# Carrier_Board.net
KiCad netlist of a schematic drawn in EAGLE
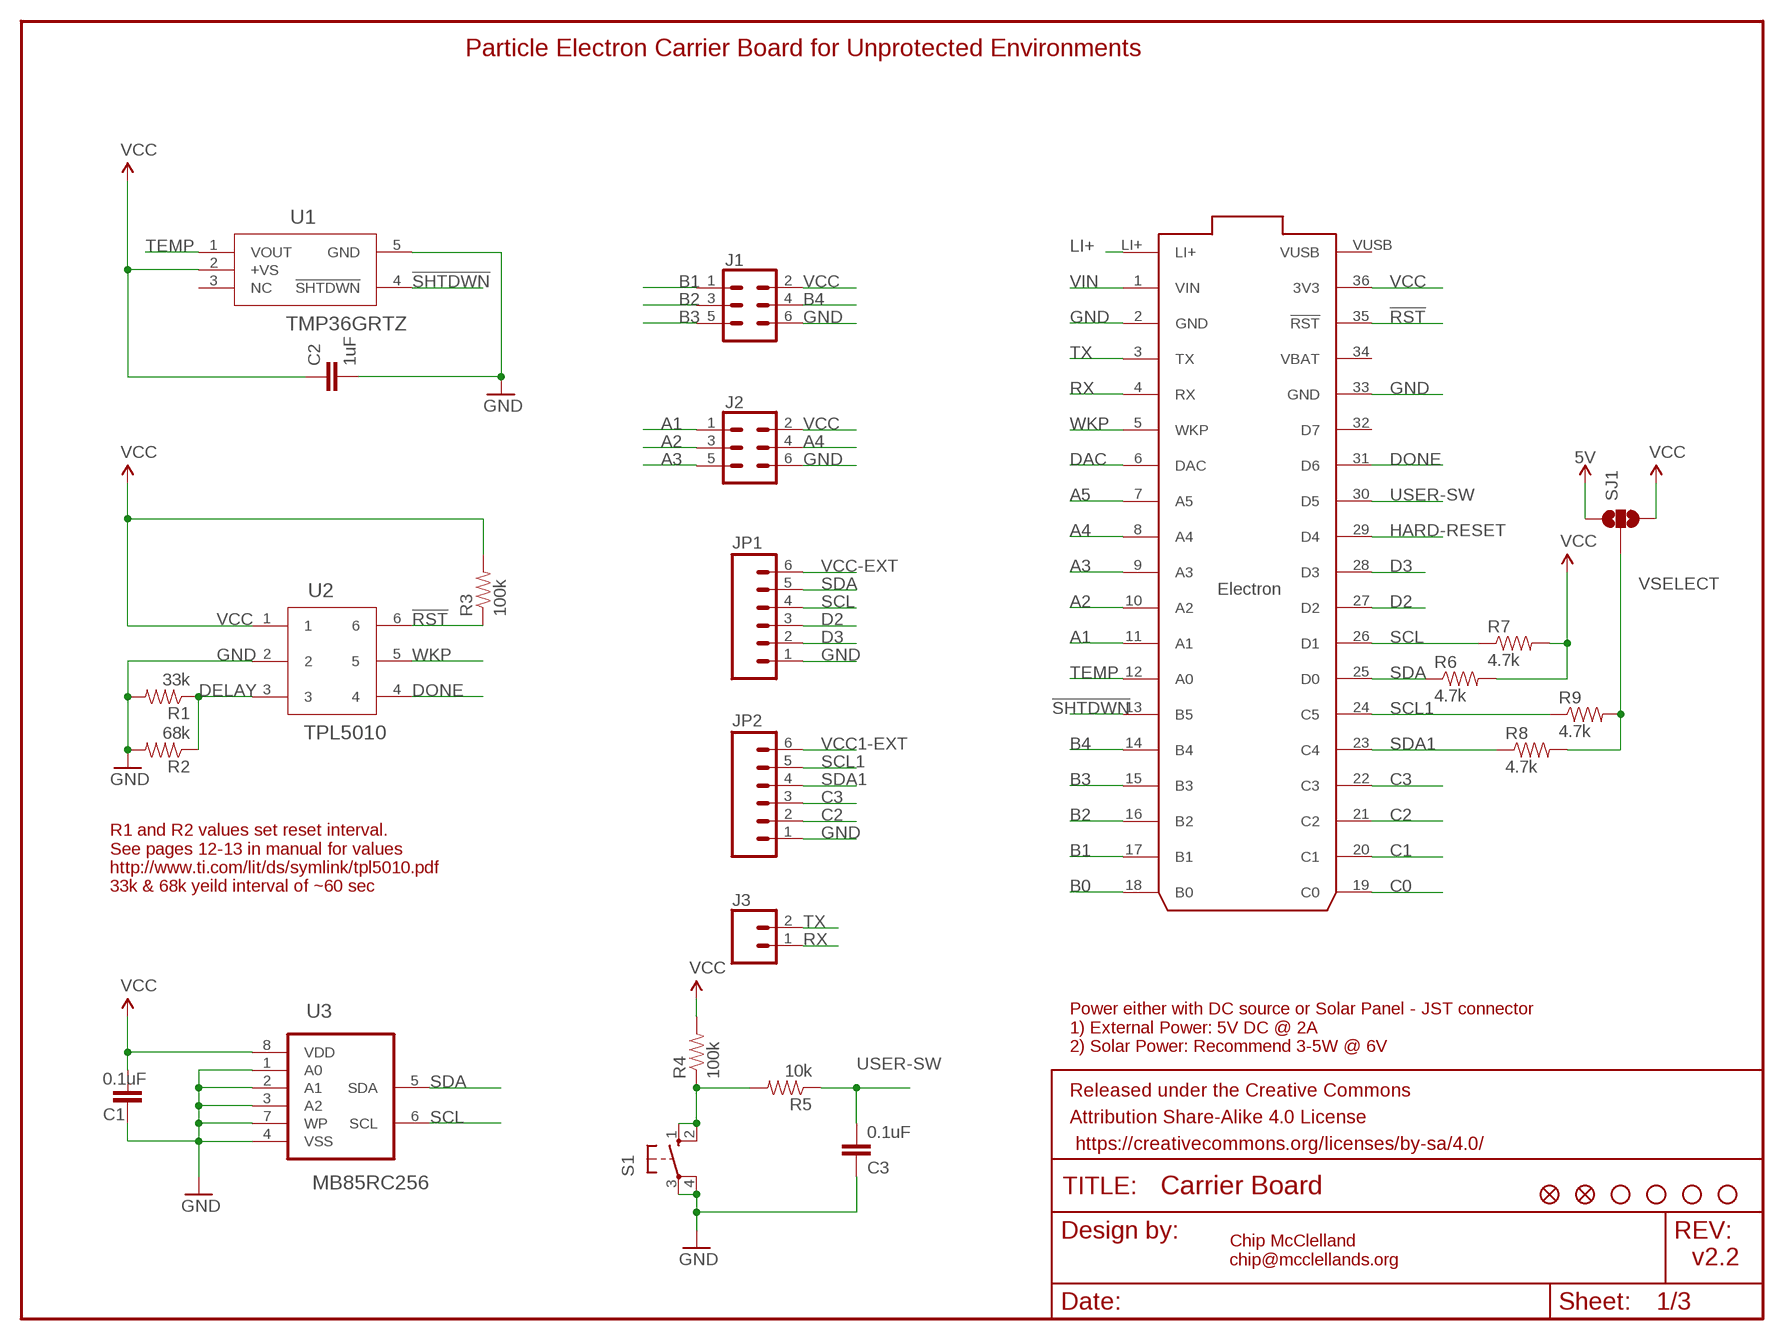
[diagram p0: schematic, sheet 1]
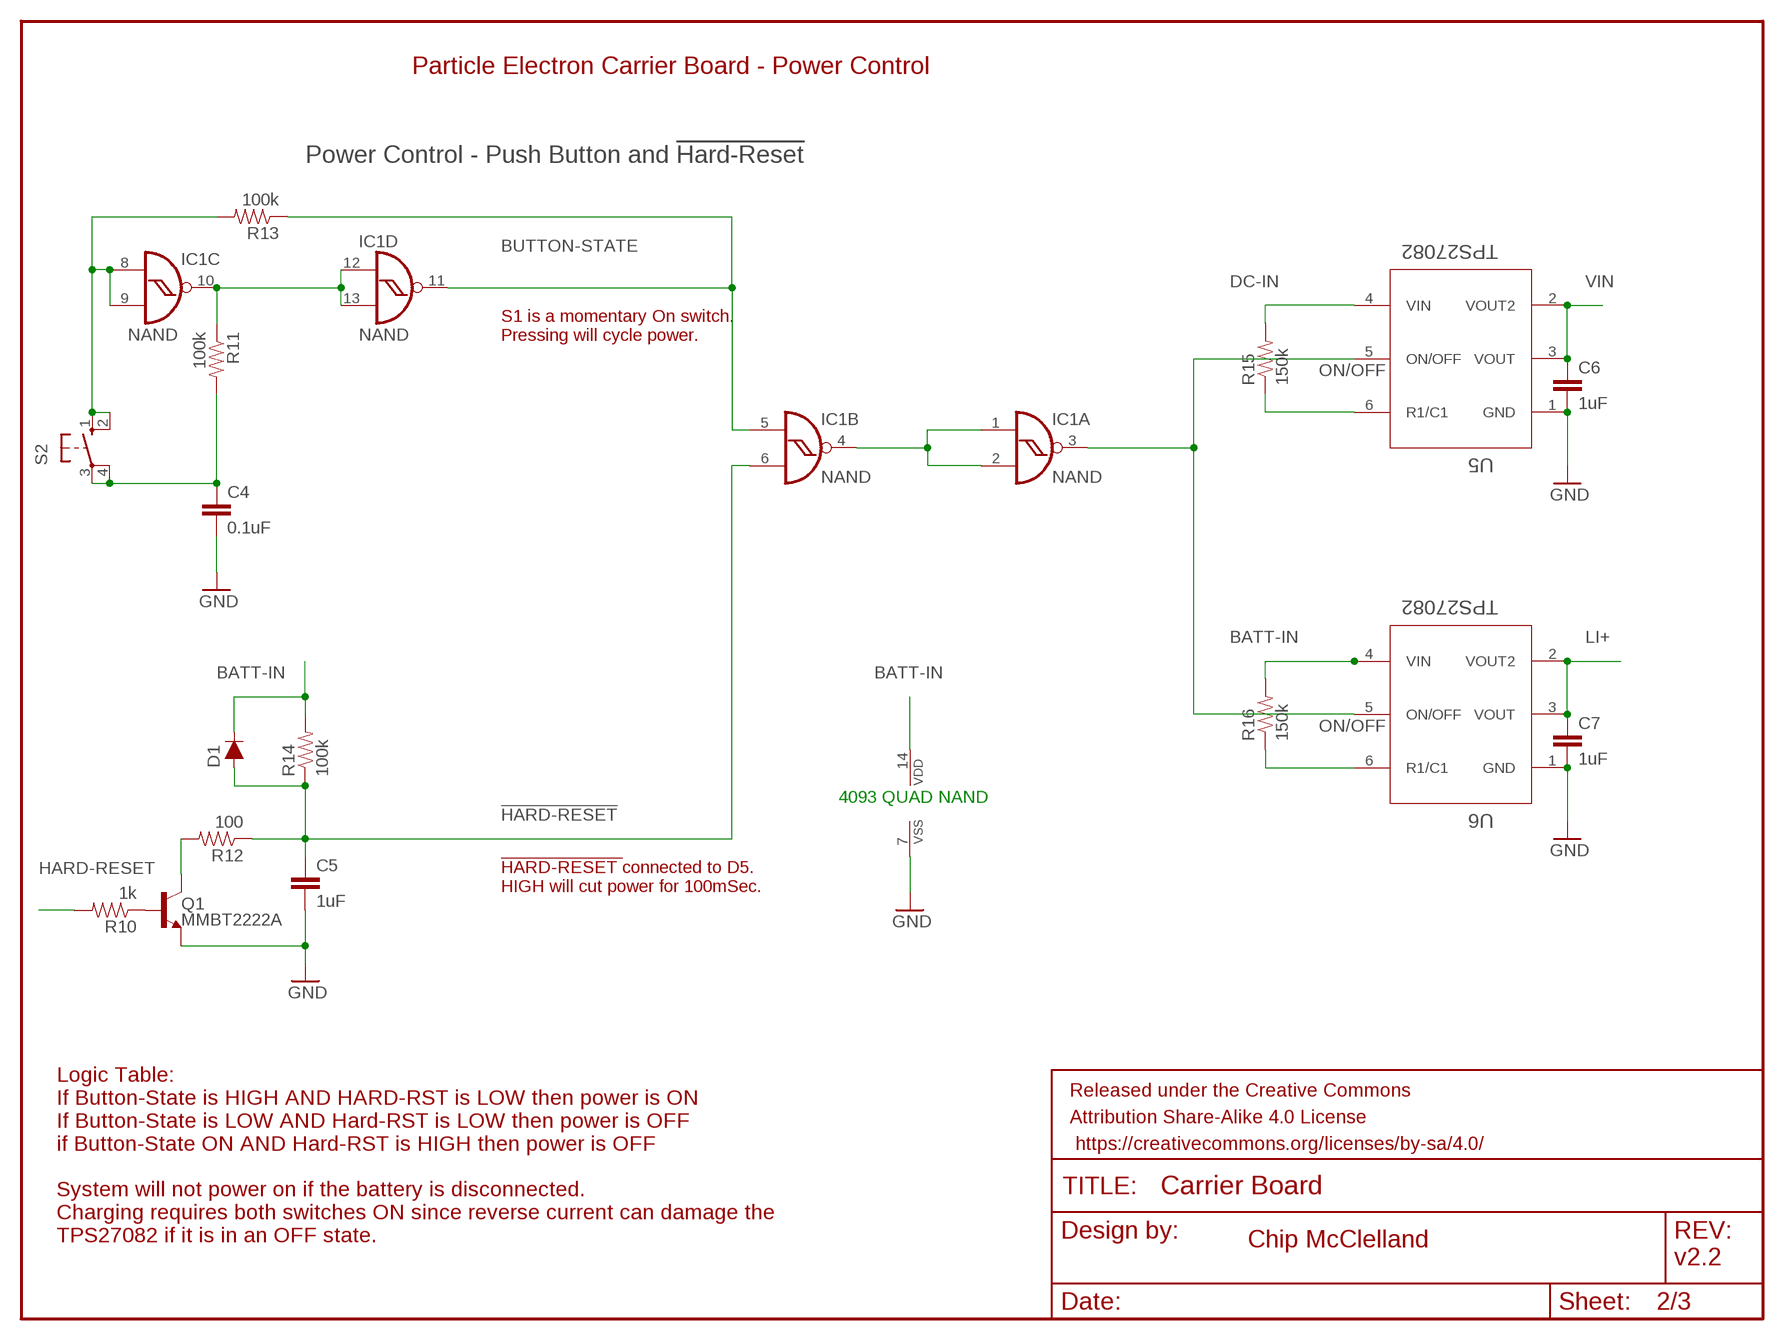
[diagram p1: schematic, sheet 2]
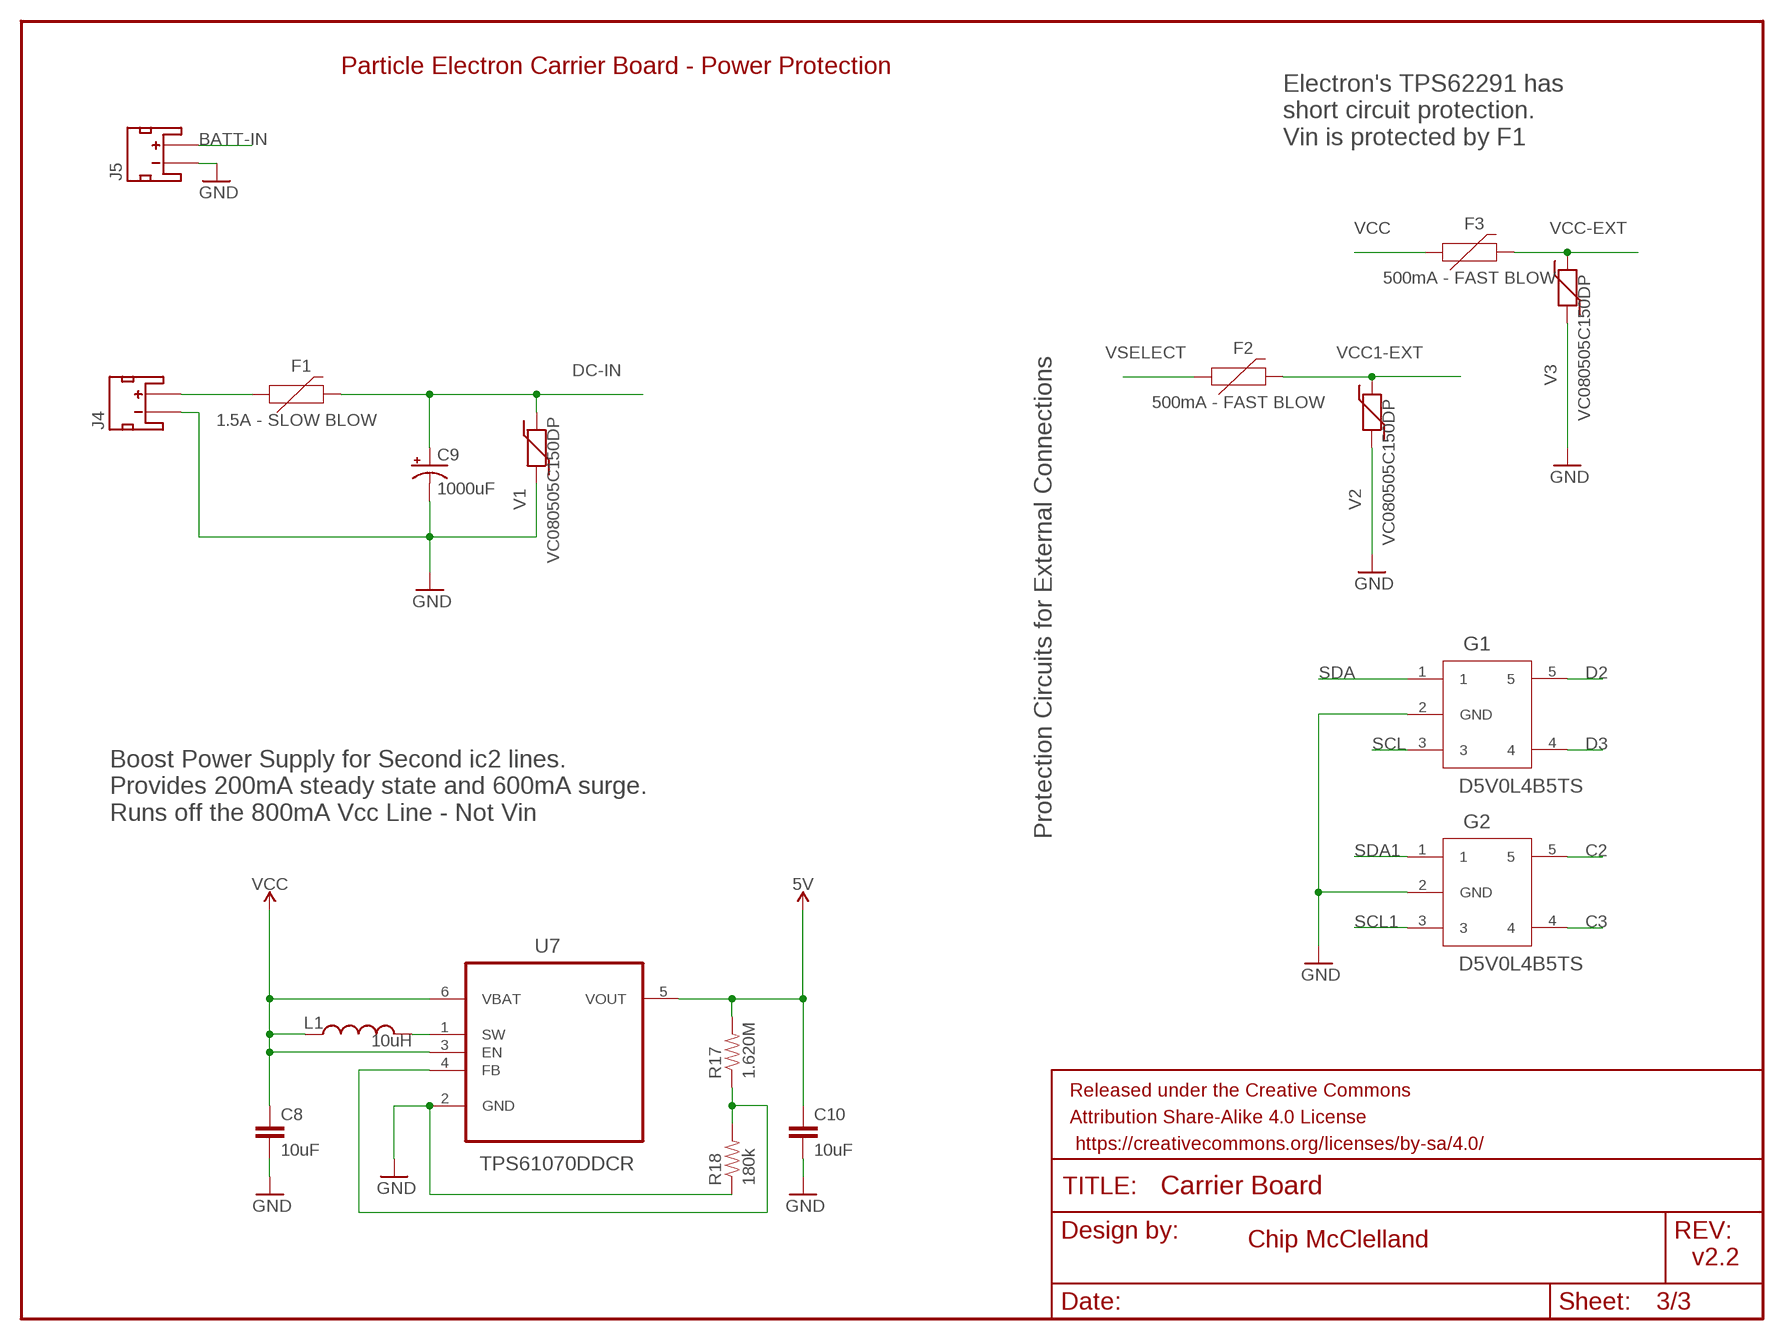
[diagram p2: schematic, sheet 3]

(export (version "E")
  (design (tool "Eeschema 10.0.6"))
  (components
    (comp (ref "C1")
      (value "0.1uF")
      (footprint "eagle-import:0805")
      (libsource (lib "eagle-import") (part "CAP0805"))
    )
    (comp (ref "C2")
      (value "1uF")
      (footprint "eagle-import:0805")
      (libsource (lib "eagle-import") (part "CAP0805"))
    )
    (comp (ref "C3")
      (value "0.1uF")
      (footprint "eagle-import:0805")
      (libsource (lib "eagle-import") (part "CAP0805"))
    )
    (comp (ref "FD1")
      (value "FIDUCIALUFIDUCIAL")
      (footprint "eagle-import:FIDUCIAL-MICRO")
      (libsource (lib "eagle-import") (part "FIDUCIALUFIDUCIAL"))
    )
    (comp (ref "FD2")
      (value "FIDUCIALUFIDUCIAL")
      (footprint "eagle-import:FIDUCIAL-MICRO")
      (libsource (lib "eagle-import") (part "FIDUCIALUFIDUCIAL"))
    )
    (comp (ref "FRAME1")
      (value "FRAME-LETTER")
      (footprint "eagle-import:CREATIVE_COMMONS")
      (libsource (lib "eagle-import") (part "FRAME-LETTER"))
    )
    (comp (ref "J1")
      (value "CONN_03X22X3_SILK_MALE_PTH")
      (footprint "eagle-import:2X3")
      (libsource (lib "eagle-import") (part "CONN_03X22X3_SILK_MALE_PTH"))
    )
    (comp (ref "J2")
      (value "CONN_03X22X3_SILK_MALE_PTH")
      (footprint "eagle-import:2X3")
      (libsource (lib "eagle-import") (part "CONN_03X22X3_SILK_MALE_PTH"))
    )
    (comp (ref "J3")
      (value "CONN_02")
      (footprint "eagle-import:1X02")
      (libsource (lib "eagle-import") (part "CONN_02"))
    )
    (comp (ref "JP1")
      (value "M06LOCK")
      (footprint "eagle-import:1X06_LOCK")
      (libsource (lib "eagle-import") (part "M06LOCK"))
    )
    (comp (ref "JP2")
      (value "M06LOCK")
      (footprint "eagle-import:1X06_LOCK")
      (libsource (lib "eagle-import") (part "M06LOCK"))
    )
    (comp (ref "JP3")
      (value "STAND-OFF")
      (footprint "eagle-import:STAND-OFF")
      (libsource (lib "eagle-import") (part "STAND-OFF"))
    )
    (comp (ref "JP4")
      (value "STAND-OFF")
      (footprint "eagle-import:STAND-OFF")
      (libsource (lib "eagle-import") (part "STAND-OFF"))
    )
    (comp (ref "JP5")
      (value "STAND-OFF")
      (footprint "eagle-import:STAND-OFF")
      (libsource (lib "eagle-import") (part "STAND-OFF"))
    )
    (comp (ref "JP6")
      (value "STAND-OFF")
      (footprint "eagle-import:STAND-OFF")
      (libsource (lib "eagle-import") (part "STAND-OFF"))
    )
    (comp (ref "R1")
      (value "33k")
      (footprint "eagle-import:0805")
      (libsource (lib "eagle-import") (part "RESISTOR0805-RES"))
    )
    (comp (ref "R2")
      (value "68k")
      (footprint "eagle-import:0805")
      (libsource (lib "eagle-import") (part "RESISTOR0805-RES"))
    )
    (comp (ref "R3")
      (value "100k")
      (footprint "eagle-import:0805")
      (libsource (lib "eagle-import") (part "RESISTOR0805-RES"))
    )
    (comp (ref "R4")
      (value "100k")
      (footprint "eagle-import:0805")
      (libsource (lib "eagle-import") (part "RESISTOR0805-RES"))
    )
    (comp (ref "R5")
      (value "10k")
      (footprint "eagle-import:0805")
      (libsource (lib "eagle-import") (part "RESISTOR0805-RES"))
    )
    (comp (ref "R6")
      (value "4.7k")
      (footprint "eagle-import:0805")
      (libsource (lib "eagle-import") (part "RESISTOR0805-RES"))
    )
    (comp (ref "R7")
      (value "4.7k")
      (footprint "eagle-import:0805")
      (libsource (lib "eagle-import") (part "RESISTOR0805-RES"))
    )
    (comp (ref "R8")
      (value "4.7k")
      (footprint "eagle-import:0805")
      (libsource (lib "eagle-import") (part "RESISTOR0805-RES"))
    )
    (comp (ref "R9")
      (value "4.7k")
      (footprint "eagle-import:0805")
      (libsource (lib "eagle-import") (part "RESISTOR0805-RES"))
    )
    (comp (ref "S1")
      (value "10-XX")
      (footprint "eagle-import:B3F-10XX")
      (libsource (lib "eagle-import") (part "10-XX"))
    )
    (comp (ref "SJ1")
      (value "SOLDERJUMPER_2WAYPASTE1&2")
      (footprint "eagle-import:SJ_3_PASTE1&2")
      (libsource (lib "eagle-import") (part "SOLDERJUMPER_2WAYPASTE1&2"))
    )
    (comp (ref "U1")
      (value "TMP36GRTZ")
      (footprint "eagle-import:RJ_5")
      (fields (field (name "MANUFACTURER_PART_NUMBER") "TMP36GRTZREEL7"))
      (libsource (lib "eagle-import") (part "TMP36GRTZ-REEL7"))
    )
    (comp (ref "U2")
      (value "TPL5010")
      (footprint "eagle-import:TSOT-23")
      (libsource (lib "eagle-import") (part "TPL5010"))
    )
    (comp (ref "U3")
      (value "MB85RC256")
      (footprint "eagle-import:SOIC127P600X175-8N")
      (fields (field (name "MPN") "MB85RC128PNF-G-JNE1"))
      (libsource (lib "eagle-import") (part "MB85RC128PNF-G-JNE1"))
    )
    (comp (ref "U4")
      (value "Particle Electron")
      (footprint "eagle-import:ELECTON-PWR-PINS")
      (libsource (lib "eagle-import") (part "ELECTRON-PWR-PINS"))
    )
    (comp (ref "C4")
      (value "0.1uF")
      (footprint "eagle-import:0805")
      (libsource (lib "eagle-import") (part "CAP0805"))
    )
    (comp (ref "C5")
      (value "1uF")
      (footprint "eagle-import:0805")
      (libsource (lib "eagle-import") (part "CAP0805"))
    )
    (comp (ref "C6")
      (value "1uF")
      (footprint "eagle-import:0805")
      (libsource (lib "eagle-import") (part "CAP0805"))
    )
    (comp (ref "C7")
      (value "1uF")
      (footprint "eagle-import:0805")
      (libsource (lib "eagle-import") (part "CAP0805"))
    )
    (comp (ref "D1")
      (value "DIODE-BAS16J")
      (footprint "eagle-import:SOD-323")
      (libsource (lib "eagle-import") (part "DIODE-BAS16J"))
    )
    (comp (ref "FRAME2")
      (value "FRAME-LETTER")
      (footprint "eagle-import:CREATIVE_COMMONS")
      (libsource (lib "eagle-import") (part "FRAME-LETTER"))
    )
    (comp (ref "IC1")
      (value "NAND")
      (footprint "eagle-import:MC14093B-TSSOP14")
      (libsource (lib "eagle-import") (part "4093DT"))
    )
    (comp (ref "Q1")
      (value "MMBT2222A")
      (footprint "eagle-import:SOT23-3")
      (libsource (lib "eagle-import") (part "TRANS_NPN-MMBT2222AL"))
    )
    (comp (ref "R10")
      (value "1k")
      (footprint "eagle-import:0805")
      (libsource (lib "eagle-import") (part "RESISTOR0805-RES"))
    )
    (comp (ref "R11")
      (value "100k")
      (footprint "eagle-import:0805")
      (libsource (lib "eagle-import") (part "RESISTOR0805-RES"))
    )
    (comp (ref "R12")
      (value "100")
      (footprint "eagle-import:0805")
      (libsource (lib "eagle-import") (part "RESISTOR0805-RES"))
    )
    (comp (ref "R13")
      (value "100k")
      (footprint "eagle-import:0805")
      (libsource (lib "eagle-import") (part "RESISTOR0805-RES"))
    )
    (comp (ref "R14")
      (value "100k")
      (footprint "eagle-import:0805")
      (libsource (lib "eagle-import") (part "RESISTOR0805-RES"))
    )
    (comp (ref "R15")
      (value "150k")
      (footprint "eagle-import:0805")
      (libsource (lib "eagle-import") (part "RESISTOR0805-RES"))
    )
    (comp (ref "R16")
      (value "150k")
      (footprint "eagle-import:0805")
      (libsource (lib "eagle-import") (part "RESISTOR0805-RES"))
    )
    (comp (ref "S2")
      (value "40-XX-ROUND")
      (footprint "eagle-import:B3F-40XX-ROUND")
      (libsource (lib "eagle-import") (part "40-XX-ROUND"))
    )
    (comp (ref "U5")
      (value "TPS27082")
      (footprint "eagle-import:TSOT-23")
      (libsource (lib "eagle-import") (part "TPS27082"))
    )
    (comp (ref "U6")
      (value "TPS27082")
      (footprint "eagle-import:TSOT-23")
      (libsource (lib "eagle-import") (part "TPS27082"))
    )
    (comp (ref "C8")
      (value "10uF")
      (footprint "eagle-import:0805")
      (libsource (lib "eagle-import") (part "CAP0805"))
    )
    (comp (ref "C9")
      (value "1000uF")
      (footprint "eagle-import:PANASONIC_G")
      (libsource (lib "eagle-import") (part "CAP_POLG"))
    )
    (comp (ref "C10")
      (value "10uF")
      (footprint "eagle-import:0805")
      (libsource (lib "eagle-import") (part "CAP0805"))
    )
    (comp (ref "F1")
      (value "1.5A - SLOW BLOW")
      (footprint "eagle-import:1206")
      (libsource (lib "eagle-import") (part "PPTC_HALF-AMP"))
    )
    (comp (ref "F2")
      (value "500mA - FAST BLOW")
      (footprint "eagle-import:1206")
      (libsource (lib "eagle-import") (part "PPTC_HALF-AMP"))
    )
    (comp (ref "F3")
      (value "500mA - FAST BLOW")
      (footprint "eagle-import:1206")
      (libsource (lib "eagle-import") (part "PPTC_HALF-AMP"))
    )
    (comp (ref "FRAME3")
      (value "FRAME-LETTER")
      (footprint "eagle-import:CREATIVE_COMMONS")
      (libsource (lib "eagle-import") (part "FRAME-LETTER"))
    )
    (comp (ref "G1")
      (value "D5V0L4B5TS")
      (footprint "eagle-import:SOT-23-5")
      (libsource (lib "eagle-import") (part "D5V0L4B5TS"))
    )
    (comp (ref "G2")
      (value "D5V0L4B5TS")
      (footprint "eagle-import:SOT-23-5")
      (libsource (lib "eagle-import") (part "D5V0L4B5TS"))
    )
    (comp (ref "J4")
      (value "5V @ 2A")
      (footprint "eagle-import:JST-2-SMD")
      (libsource (lib "eagle-import") (part "JST_2MM_MALE"))
    )
    (comp (ref "J5")
      (value "JST_2MM_MALE")
      (footprint "eagle-import:JST-2-SMD")
      (libsource (lib "eagle-import") (part "JST_2MM_MALE"))
    )
    (comp (ref "L1")
      (value "10uH")
      (footprint "eagle-import:SDR0403")
      (libsource (lib "eagle-import") (part "INDUCTORSDR0403-560KL"))
    )
    (comp (ref "R17")
      (value "1.620M")
      (footprint "eagle-import:0805")
      (libsource (lib "eagle-import") (part "RESISTOR0805-RES"))
    )
    (comp (ref "R18")
      (value "180k")
      (footprint "eagle-import:0805")
      (libsource (lib "eagle-import") (part "RESISTOR0805-RES"))
    )
    (comp (ref "U7")
      (value "TPS61070DDCR")
      (footprint "eagle-import:SOT95P280X110-6N")
      (libsource (lib "eagle-import") (part "TPS61070DDCR"))
    )
    (comp (ref "V1")
      (value "VC080505C150DP")
      (footprint "eagle-import:0805")
      (libsource (lib "eagle-import") (part "VARISTOR"))
    )
    (comp (ref "V2")
      (value "VC080505C150DP")
      (footprint "eagle-import:0805")
      (libsource (lib "eagle-import") (part "VARISTOR"))
    )
    (comp (ref "V3")
      (value "VC080505C150DP")
      (footprint "eagle-import:0805")
      (libsource (lib "eagle-import") (part "VARISTOR"))
    )
  )
  (nets
    (net (code "1") (name "5V") (class "Default")
      (node (ref "C10") (pin "1") (pinfunction "1_1") (pintype "passive"))
      (node (ref "R17") (pin "2") (pinfunction "2_2") (pintype "passive"))
      (node (ref "SJ1") (pin "1") (pinfunction "1_1") (pintype "passive"))
      (node (ref "U7") (pin "5") (pinfunction "VOUT_5") (pintype "output"))
    )
    (net (code "2") (name "A1") (class "Default")
      (node (ref "J2") (pin "1") (pinfunction "1_1") (pintype "bidirectional"))
      (node (ref "U4") (pin "11") (pinfunction "A1_11") (pintype "bidirectional"))
    )
    (net (code "3") (name "A2") (class "Default")
      (node (ref "J2") (pin "3") (pinfunction "3_3") (pintype "bidirectional"))
      (node (ref "U4") (pin "10") (pinfunction "A2_10") (pintype "bidirectional"))
    )
    (net (code "4") (name "A3") (class "Default")
      (node (ref "J2") (pin "5") (pinfunction "5_5") (pintype "bidirectional"))
      (node (ref "U4") (pin "9") (pinfunction "A3_9") (pintype "bidirectional"))
    )
    (net (code "5") (name "A4") (class "Default")
      (node (ref "J2") (pin "4") (pinfunction "4_4") (pintype "bidirectional"))
      (node (ref "U4") (pin "8") (pinfunction "A4_8") (pintype "bidirectional"))
    )
    (net (code "6") (name "A5") (class "Default")
      (node (ref "U4") (pin "7") (pinfunction "A5_7") (pintype "bidirectional"))
    )
    (net (code "7") (name "B0") (class "Default")
      (node (ref "U4") (pin "18") (pinfunction "B0_18") (pintype "bidirectional"))
    )
    (net (code "8") (name "B1") (class "Default")
      (node (ref "J1") (pin "1") (pinfunction "1_1") (pintype "bidirectional"))
      (node (ref "U4") (pin "17") (pinfunction "B1_17") (pintype "bidirectional"))
    )
    (net (code "9") (name "B2") (class "Default")
      (node (ref "J1") (pin "3") (pinfunction "3_3") (pintype "bidirectional"))
      (node (ref "U4") (pin "16") (pinfunction "B2_16") (pintype "bidirectional"))
    )
    (net (code "10") (name "B3") (class "Default")
      (node (ref "J1") (pin "5") (pinfunction "5_5") (pintype "bidirectional"))
      (node (ref "U4") (pin "15") (pinfunction "B3_15") (pintype "bidirectional"))
    )
    (net (code "11") (name "B4") (class "Default")
      (node (ref "J1") (pin "4") (pinfunction "4_4") (pintype "bidirectional"))
      (node (ref "U4") (pin "14") (pinfunction "B4_14") (pintype "bidirectional"))
    )
    (net (code "12") (name "BATT-IN") (class "Default")
      (node (ref "D1") (pin "C") (pinfunction "C_C") (pintype "passive"))
      (node (ref "IC1") (pin "14") (pinfunction "VDD_14") (pintype "power_in"))
      (node (ref "J5") (pin "2") (pinfunction "+_2") (pintype "bidirectional"))
      (node (ref "R14") (pin "2") (pinfunction "2_2") (pintype "passive"))
      (node (ref "R16") (pin "2") (pinfunction "2_2") (pintype "passive"))
      (node (ref "U6") (pin "4") (pinfunction "VIN_4") (pintype "input"))
    )
    (net (code "13") (name "BUTTON-STATE") (class "Default")
      (node (ref "IC1") (pin "11") (pinfunction "O_11") (pintype "output"))
      (node (ref "IC1") (pin "5") (pinfunction "I0_5") (pintype "input"))
      (node (ref "R13") (pin "1") (pinfunction "1_1") (pintype "passive"))
    )
    (net (code "14") (name "C0") (class "Default")
      (node (ref "U4") (pin "19") (pinfunction "C0_19") (pintype "bidirectional"))
    )
    (net (code "15") (name "C1") (class "Default")
      (node (ref "U4") (pin "20") (pinfunction "C1_20") (pintype "bidirectional"))
    )
    (net (code "16") (name "C2") (class "Default")
      (node (ref "G2") (pin "5") (pinfunction "5_5") (pintype "power_in"))
      (node (ref "JP2") (pin "2") (pinfunction "2_2") (pintype "passive"))
      (node (ref "U4") (pin "21") (pinfunction "C2_21") (pintype "bidirectional"))
    )
    (net (code "17") (name "C3") (class "Default")
      (node (ref "G2") (pin "4") (pinfunction "4_4") (pintype "input"))
      (node (ref "JP2") (pin "3") (pinfunction "3_3") (pintype "passive"))
      (node (ref "U4") (pin "22") (pinfunction "C3_22") (pintype "bidirectional"))
    )
    (net (code "18") (name "D2") (class "Default")
      (node (ref "G1") (pin "5") (pinfunction "5_5") (pintype "power_in"))
      (node (ref "JP1") (pin "3") (pinfunction "3_3") (pintype "passive"))
      (node (ref "U4") (pin "27") (pinfunction "D2_27") (pintype "bidirectional"))
    )
    (net (code "19") (name "D3") (class "Default")
      (node (ref "G1") (pin "4") (pinfunction "4_4") (pintype "input"))
      (node (ref "JP1") (pin "2") (pinfunction "2_2") (pintype "passive"))
      (node (ref "U4") (pin "28") (pinfunction "D3_28") (pintype "bidirectional"))
    )
    (net (code "20") (name "DAC") (class "Default")
      (node (ref "U4") (pin "6") (pinfunction "DAC_6") (pintype "bidirectional"))
    )
    (net (code "21") (name "DC-IN") (class "Default")
      (node (ref "C9") (pin "+") (pinfunction "+_+") (pintype "passive"))
      (node (ref "F1") (pin "2") (pinfunction "2_2") (pintype "bidirectional"))
      (node (ref "R15") (pin "2") (pinfunction "2_2") (pintype "passive"))
      (node (ref "U5") (pin "4") (pinfunction "VIN_4") (pintype "input"))
      (node (ref "V1") (pin "2") (pinfunction "2_2") (pintype "passive"))
    )
    (net (code "22") (name "DELAY") (class "Default")
      (node (ref "R1") (pin "1") (pinfunction "1_1") (pintype "passive"))
      (node (ref "R2") (pin "1") (pinfunction "1_1") (pintype "passive"))
      (node (ref "U2") (pin "3") (pinfunction "3_3") (pintype "power_in"))
    )
    (net (code "23") (name "DONE") (class "Default")
      (node (ref "U2") (pin "4") (pinfunction "4_4") (pintype "input"))
      (node (ref "U4") (pin "31") (pinfunction "D6_31") (pintype "bidirectional"))
    )
    (net (code "24") (name "GND") (class "Default")
      (node (ref "C1") (pin "2") (pinfunction "2_2") (pintype "passive"))
      (node (ref "C10") (pin "2") (pinfunction "2_2") (pintype "passive"))
      (node (ref "C2") (pin "2") (pinfunction "2_2") (pintype "passive"))
      (node (ref "C3") (pin "2") (pinfunction "2_2") (pintype "passive"))
      (node (ref "C4") (pin "2") (pinfunction "2_2") (pintype "passive"))
      (node (ref "C5") (pin "2") (pinfunction "2_2") (pintype "passive"))
      (node (ref "C6") (pin "2") (pinfunction "2_2") (pintype "passive"))
      (node (ref "C7") (pin "2") (pinfunction "2_2") (pintype "passive"))
      (node (ref "C8") (pin "2") (pinfunction "2_2") (pintype "passive"))
      (node (ref "C9") (pin "-") (pinfunction "-_-") (pintype "passive"))
      (node (ref "G1") (pin "2") (pinfunction "GND_2") (pintype "input"))
      (node (ref "G2") (pin "2") (pinfunction "GND_2") (pintype "input"))
      (node (ref "IC1") (pin "7") (pinfunction "VSS_7") (pintype "power_in"))
      (node (ref "J1") (pin "6") (pinfunction "6_6") (pintype "bidirectional"))
      (node (ref "J2") (pin "6") (pinfunction "6_6") (pintype "bidirectional"))
      (node (ref "J4") (pin "1") (pinfunction "-_1") (pintype "bidirectional"))
      (node (ref "J5") (pin "1") (pinfunction "-_1") (pintype "bidirectional"))
      (node (ref "JP1") (pin "1") (pinfunction "1_1") (pintype "passive"))
      (node (ref "JP2") (pin "1") (pinfunction "1_1") (pintype "passive"))
      (node (ref "Q1") (pin "2") (pinfunction "E_2") (pintype "passive"))
      (node (ref "R1") (pin "2") (pinfunction "2_2") (pintype "passive"))
      (node (ref "R18") (pin "1") (pinfunction "1_1") (pintype "passive"))
      (node (ref "R2") (pin "2") (pinfunction "2_2") (pintype "passive"))
      (node (ref "S1") (pin "3") (pinfunction "P_3") (pintype "passive"))
      (node (ref "S1") (pin "4") (pinfunction "P1_4") (pintype "passive"))
      (node (ref "U1") (pin "5") (pinfunction "GND_5") (pintype "passive"))
      (node (ref "U2") (pin "2") (pinfunction "2_2") (pintype "input"))
      (node (ref "U3") (pin "1") (pinfunction "A0_1") (pintype "input"))
      (node (ref "U3") (pin "2") (pinfunction "A1_2") (pintype "input"))
      (node (ref "U3") (pin "3") (pinfunction "A2_3") (pintype "input"))
      (node (ref "U3") (pin "4") (pinfunction "VSS_4") (pintype "passive"))
      (node (ref "U3") (pin "7") (pinfunction "WP_7") (pintype "input"))
      (node (ref "U4") (pin "2") (pinfunction "GND_2") (pintype "power_in"))
      (node (ref "U4") (pin "33") (pinfunction "GND_33") (pintype "power_in"))
      (node (ref "U5") (pin "1") (pinfunction "GND_1") (pintype "power_in"))
      (node (ref "U6") (pin "1") (pinfunction "GND_1") (pintype "power_in"))
      (node (ref "U7") (pin "2") (pinfunction "GND_2") (pintype "passive"))
      (node (ref "V1") (pin "1") (pinfunction "1_1") (pintype "passive"))
      (node (ref "V2") (pin "1") (pinfunction "1_1") (pintype "passive"))
      (node (ref "V3") (pin "1") (pinfunction "1_1") (pintype "passive"))
    )
    (net (code "25") (name "HARD-RESET") (class "Default")
      (node (ref "R10") (pin "2") (pinfunction "2_2") (pintype "passive"))
      (node (ref "U4") (pin "29") (pinfunction "D4_29") (pintype "bidirectional"))
    )
    (net (code "26") (name "LI+") (class "Default")
      (node (ref "C7") (pin "1") (pinfunction "1_1") (pintype "passive"))
      (node (ref "U4") (pin "LI+") (pinfunction "LI+_LI+") (pintype "bidirectional"))
      (node (ref "U6") (pin "2") (pinfunction "VOUT2_2") (pintype "power_in"))
      (node (ref "U6") (pin "3") (pinfunction "VOUT_3") (pintype "input"))
    )
    (net (code "27") (name "Net-(IC1A-I0)") (class "Default")
      (node (ref "IC1") (pin "1") (pinfunction "I0_1") (pintype "input"))
      (node (ref "IC1") (pin "2") (pinfunction "I1_2") (pintype "input"))
      (node (ref "IC1") (pin "4") (pinfunction "O_4") (pintype "output"))
    )
    (net (code "28") (name "Net-(IC1C-I0)") (class "Default")
      (node (ref "IC1") (pin "8") (pinfunction "I0_8") (pintype "input"))
      (node (ref "IC1") (pin "9") (pinfunction "I1_9") (pintype "input"))
      (node (ref "R13") (pin "2") (pinfunction "2_2") (pintype "passive"))
      (node (ref "S2") (pin "1") (pinfunction "S_1") (pintype "passive"))
      (node (ref "S2") (pin "2") (pinfunction "S1_2") (pintype "passive"))
    )
    (net (code "29") (name "Net-(IC1C-O)") (class "Default")
      (node (ref "IC1") (pin "10") (pinfunction "O_10") (pintype "output"))
      (node (ref "IC1") (pin "12") (pinfunction "I0_12") (pintype "input"))
      (node (ref "IC1") (pin "13") (pinfunction "I1_13") (pintype "input"))
      (node (ref "R11") (pin "1") (pinfunction "1_1") (pintype "passive"))
    )
    (net (code "30") (name "Net-(J4-+)") (class "Default")
      (node (ref "F1") (pin "1") (pinfunction "1_1") (pintype "bidirectional"))
      (node (ref "J4") (pin "2") (pinfunction "+_2") (pintype "bidirectional"))
    )
    (net (code "31") (name "Net-(L1-2)") (class "Default")
      (node (ref "L1") (pin "P$2") (pinfunction "2_P$2") (pintype "passive"))
      (node (ref "U7") (pin "1") (pinfunction "SW_1") (pintype "input"))
    )
    (net (code "32") (name "Net-(Q1-B)") (class "Default")
      (node (ref "Q1") (pin "1") (pinfunction "B_1") (pintype "passive"))
      (node (ref "R10") (pin "1") (pinfunction "1_1") (pintype "passive"))
    )
    (net (code "33") (name "Net-(Q1-C)") (class "Default")
      (node (ref "Q1") (pin "3") (pinfunction "C_3") (pintype "passive"))
      (node (ref "R12") (pin "2") (pinfunction "2_2") (pintype "passive"))
    )
    (net (code "34") (name "Net-(S1-S)") (class "Default")
      (node (ref "R4") (pin "1") (pinfunction "1_1") (pintype "passive"))
      (node (ref "R5") (pin "2") (pinfunction "2_2") (pintype "passive"))
      (node (ref "S1") (pin "1") (pinfunction "S_1") (pintype "passive"))
      (node (ref "S1") (pin "2") (pinfunction "S1_2") (pintype "passive"))
    )
    (net (code "35") (name "Net-(S2-P)") (class "Default")
      (node (ref "C4") (pin "1") (pinfunction "1_1") (pintype "passive"))
      (node (ref "R11") (pin "2") (pinfunction "2_2") (pintype "passive"))
      (node (ref "S2") (pin "3") (pinfunction "P_3") (pintype "passive"))
      (node (ref "S2") (pin "4") (pinfunction "P1_4") (pintype "passive"))
    )
    (net (code "36") (name "Net-(U5-R1{slash}C1)") (class "Default")
      (node (ref "R15") (pin "1") (pinfunction "1_1") (pintype "passive"))
      (node (ref "U5") (pin "6") (pinfunction "R1/C1_6") (pintype "power_in"))
    )
    (net (code "37") (name "Net-(U6-R1{slash}C1)") (class "Default")
      (node (ref "R16") (pin "1") (pinfunction "1_1") (pintype "passive"))
      (node (ref "U6") (pin "6") (pinfunction "R1/C1_6") (pintype "power_in"))
    )
    (net (code "38") (name "Net-(U7-FB)") (class "Default")
      (node (ref "R17") (pin "1") (pinfunction "1_1") (pintype "passive"))
      (node (ref "R18") (pin "2") (pinfunction "2_2") (pintype "passive"))
      (node (ref "U7") (pin "4") (pinfunction "FB_4") (pintype "input"))
    )
    (net (code "39") (name "ON{slash}OFF") (class "Default")
      (node (ref "IC1") (pin "3") (pinfunction "O_3") (pintype "output"))
      (node (ref "U5") (pin "5") (pinfunction "ON/OFF_5") (pintype "bidirectional"))
      (node (ref "U6") (pin "5") (pinfunction "ON/OFF_5") (pintype "bidirectional"))
    )
    (net (code "40") (name "RX") (class "Default")
      (node (ref "J3") (pin "1") (pinfunction "1_1") (pintype "passive"))
      (node (ref "U4") (pin "4") (pinfunction "RX_4") (pintype "bidirectional"))
    )
    (net (code "41") (name "SCL") (class "Default")
      (node (ref "G1") (pin "3") (pinfunction "3_3") (pintype "power_in"))
      (node (ref "JP1") (pin "4") (pinfunction "4_4") (pintype "passive"))
      (node (ref "R7") (pin "1") (pinfunction "1_1") (pintype "passive"))
      (node (ref "U3") (pin "6") (pinfunction "SCL_6") (pintype "input"))
      (node (ref "U4") (pin "26") (pinfunction "D1_26") (pintype "bidirectional"))
    )
    (net (code "42") (name "SCL1") (class "Default")
      (node (ref "G2") (pin "3") (pinfunction "3_3") (pintype "power_in"))
      (node (ref "JP2") (pin "5") (pinfunction "5_5") (pintype "passive"))
      (node (ref "R9") (pin "1") (pinfunction "1_1") (pintype "passive"))
      (node (ref "U4") (pin "24") (pinfunction "C5_24") (pintype "bidirectional"))
    )
    (net (code "43") (name "SDA") (class "Default")
      (node (ref "G1") (pin "1") (pinfunction "1_1") (pintype "power_in"))
      (node (ref "JP1") (pin "5") (pinfunction "5_5") (pintype "passive"))
      (node (ref "R6") (pin "1") (pinfunction "1_1") (pintype "passive"))
      (node (ref "U3") (pin "5") (pinfunction "SDA_5") (pintype "bidirectional"))
      (node (ref "U4") (pin "25") (pinfunction "D0_25") (pintype "bidirectional"))
    )
    (net (code "44") (name "SDA1") (class "Default")
      (node (ref "G2") (pin "1") (pinfunction "1_1") (pintype "power_in"))
      (node (ref "JP2") (pin "4") (pinfunction "4_4") (pintype "passive"))
      (node (ref "R8") (pin "1") (pinfunction "1_1") (pintype "passive"))
      (node (ref "U4") (pin "23") (pinfunction "C4_23") (pintype "bidirectional"))
    )
    (net (code "45") (name "TEMP") (class "Default")
      (node (ref "U1") (pin "1") (pinfunction "VOUT_1") (pintype "passive"))
      (node (ref "U4") (pin "12") (pinfunction "A0_12") (pintype "bidirectional"))
    )
    (net (code "46") (name "TX") (class "Default")
      (node (ref "J3") (pin "2") (pinfunction "2_2") (pintype "passive"))
      (node (ref "U4") (pin "3") (pinfunction "TX_3") (pintype "bidirectional"))
    )
    (net (code "47") (name "USER-SW") (class "Default")
      (node (ref "C3") (pin "1") (pinfunction "1_1") (pintype "passive"))
      (node (ref "R5") (pin "1") (pinfunction "1_1") (pintype "passive"))
      (node (ref "U4") (pin "30") (pinfunction "D5_30") (pintype "bidirectional"))
    )
    (net (code "48") (name "VBAT") (class "Default")
      (node (ref "U4") (pin "34") (pinfunction "VBAT_34") (pintype "power_in"))
    )
    (net (code "49") (name "VCC") (class "Default")
      (node (ref "C1") (pin "1") (pinfunction "1_1") (pintype "passive"))
      (node (ref "C2") (pin "1") (pinfunction "1_1") (pintype "passive"))
      (node (ref "C8") (pin "1") (pinfunction "1_1") (pintype "passive"))
      (node (ref "F3") (pin "1") (pinfunction "1_1") (pintype "bidirectional"))
      (node (ref "J1") (pin "2") (pinfunction "2_2") (pintype "bidirectional"))
      (node (ref "J2") (pin "2") (pinfunction "2_2") (pintype "bidirectional"))
      (node (ref "L1") (pin "P$1") (pinfunction "1_P$1") (pintype "passive"))
      (node (ref "R3") (pin "2") (pinfunction "2_2") (pintype "passive"))
      (node (ref "R4") (pin "2") (pinfunction "2_2") (pintype "passive"))
      (node (ref "R6") (pin "2") (pinfunction "2_2") (pintype "passive"))
      (node (ref "R7") (pin "2") (pinfunction "2_2") (pintype "passive"))
      (node (ref "SJ1") (pin "3") (pinfunction "3_3") (pintype "passive"))
      (node (ref "U1") (pin "2") (pinfunction "+VS_2") (pintype "power_in"))
      (node (ref "U2") (pin "1") (pinfunction "1_1") (pintype "power_in"))
      (node (ref "U3") (pin "8") (pinfunction "VDD_8") (pintype "power_in"))
      (node (ref "U4") (pin "36") (pinfunction "3V3_36") (pintype "power_in"))
      (node (ref "U7") (pin "3") (pinfunction "EN_3") (pintype "input"))
      (node (ref "U7") (pin "6") (pinfunction "VBAT_6") (pintype "power_in"))
    )
    (net (code "50") (name "VCC-EXT") (class "Default")
      (node (ref "F3") (pin "2") (pinfunction "2_2") (pintype "bidirectional"))
      (node (ref "JP1") (pin "6") (pinfunction "6_6") (pintype "passive"))
      (node (ref "V3") (pin "2") (pinfunction "2_2") (pintype "passive"))
    )
    (net (code "51") (name "VCC1-EXT") (class "Default")
      (node (ref "F2") (pin "2") (pinfunction "2_2") (pintype "bidirectional"))
      (node (ref "JP2") (pin "6") (pinfunction "6_6") (pintype "passive"))
      (node (ref "V2") (pin "2") (pinfunction "2_2") (pintype "passive"))
    )
    (net (code "52") (name "VIN") (class "Default")
      (node (ref "C6") (pin "1") (pinfunction "1_1") (pintype "passive"))
      (node (ref "U4") (pin "1") (pinfunction "VIN_1") (pintype "power_in"))
      (node (ref "U5") (pin "2") (pinfunction "VOUT2_2") (pintype "power_in"))
      (node (ref "U5") (pin "3") (pinfunction "VOUT_3") (pintype "input"))
    )
    (net (code "53") (name "VSELECT") (class "Default")
      (node (ref "F2") (pin "1") (pinfunction "1_1") (pintype "bidirectional"))
      (node (ref "R8") (pin "2") (pinfunction "2_2") (pintype "passive"))
      (node (ref "R9") (pin "2") (pinfunction "2_2") (pintype "passive"))
      (node (ref "SJ1") (pin "2") (pinfunction "2_2") (pintype "passive"))
    )
    (net (code "54") (name "WKP") (class "Default")
      (node (ref "U2") (pin "5") (pinfunction "5_5") (pintype "bidirectional"))
      (node (ref "U4") (pin "5") (pinfunction "WKP_5") (pintype "bidirectional"))
    )
    (net (code "55") (name "unconnected-(J4-PAD1-PadNC1)") (class "Default")
      (node (ref "J4") (pin "NC1") (pinfunction "PAD1_NC1") (pintype "bidirectional"))
    )
    (net (code "56") (name "unconnected-(J4-PAD2-PadNC2)") (class "Default")
      (node (ref "J4") (pin "NC2") (pinfunction "PAD2_NC2") (pintype "bidirectional"))
    )
    (net (code "57") (name "unconnected-(J5-PAD1-PadNC1)") (class "Default")
      (node (ref "J5") (pin "NC1") (pinfunction "PAD1_NC1") (pintype "bidirectional"))
    )
    (net (code "58") (name "unconnected-(J5-PAD2-PadNC2)") (class "Default")
      (node (ref "J5") (pin "NC2") (pinfunction "PAD2_NC2") (pintype "bidirectional"))
    )
    (net (code "59") (name "unconnected-(U1-NC-Pad3)") (class "Default")
      (node (ref "U1") (pin "3") (pinfunction "NC_3") (pintype "passive"))
    )
    (net (code "60") (name "unconnected-(U4-D7-Pad32)") (class "Default")
      (node (ref "U4") (pin "32") (pinfunction "D7_32") (pintype "bidirectional"))
    )
    (net (code "61") (name "unconnected-(U4-PadVUSB)") (class "Default")
      (node (ref "U4") (pin "VUSB") (pinfunction "VUSB_VUSB") (pintype "bidirectional"))
    )
    (net (code "62") (name "~{HARD-RESET}") (class "Default")
      (node (ref "C5") (pin "1") (pinfunction "1_1") (pintype "passive"))
      (node (ref "D1") (pin "A") (pinfunction "A_A") (pintype "passive"))
      (node (ref "IC1") (pin "6") (pinfunction "I1_6") (pintype "input"))
      (node (ref "R12") (pin "1") (pinfunction "1_1") (pintype "passive"))
      (node (ref "R14") (pin "1") (pinfunction "1_1") (pintype "passive"))
    )
    (net (code "63") (name "~{RST}") (class "Default")
      (node (ref "R3") (pin "1") (pinfunction "1_1") (pintype "passive"))
      (node (ref "U2") (pin "6") (pinfunction "6_6") (pintype "power_in"))
      (node (ref "U4") (pin "35") (pinfunction "~{RST}_35") (pintype "bidirectional"))
    )
    (net (code "64") (name "~{SHTDWN}") (class "Default")
      (node (ref "U1") (pin "4") (pinfunction "~{SHTDWN}_4") (pintype "passive"))
      (node (ref "U4") (pin "13") (pinfunction "B5_13") (pintype "bidirectional"))
    )
  )
)
